# main.net
KiCad netlist of a schematic drawn in Altium Designer
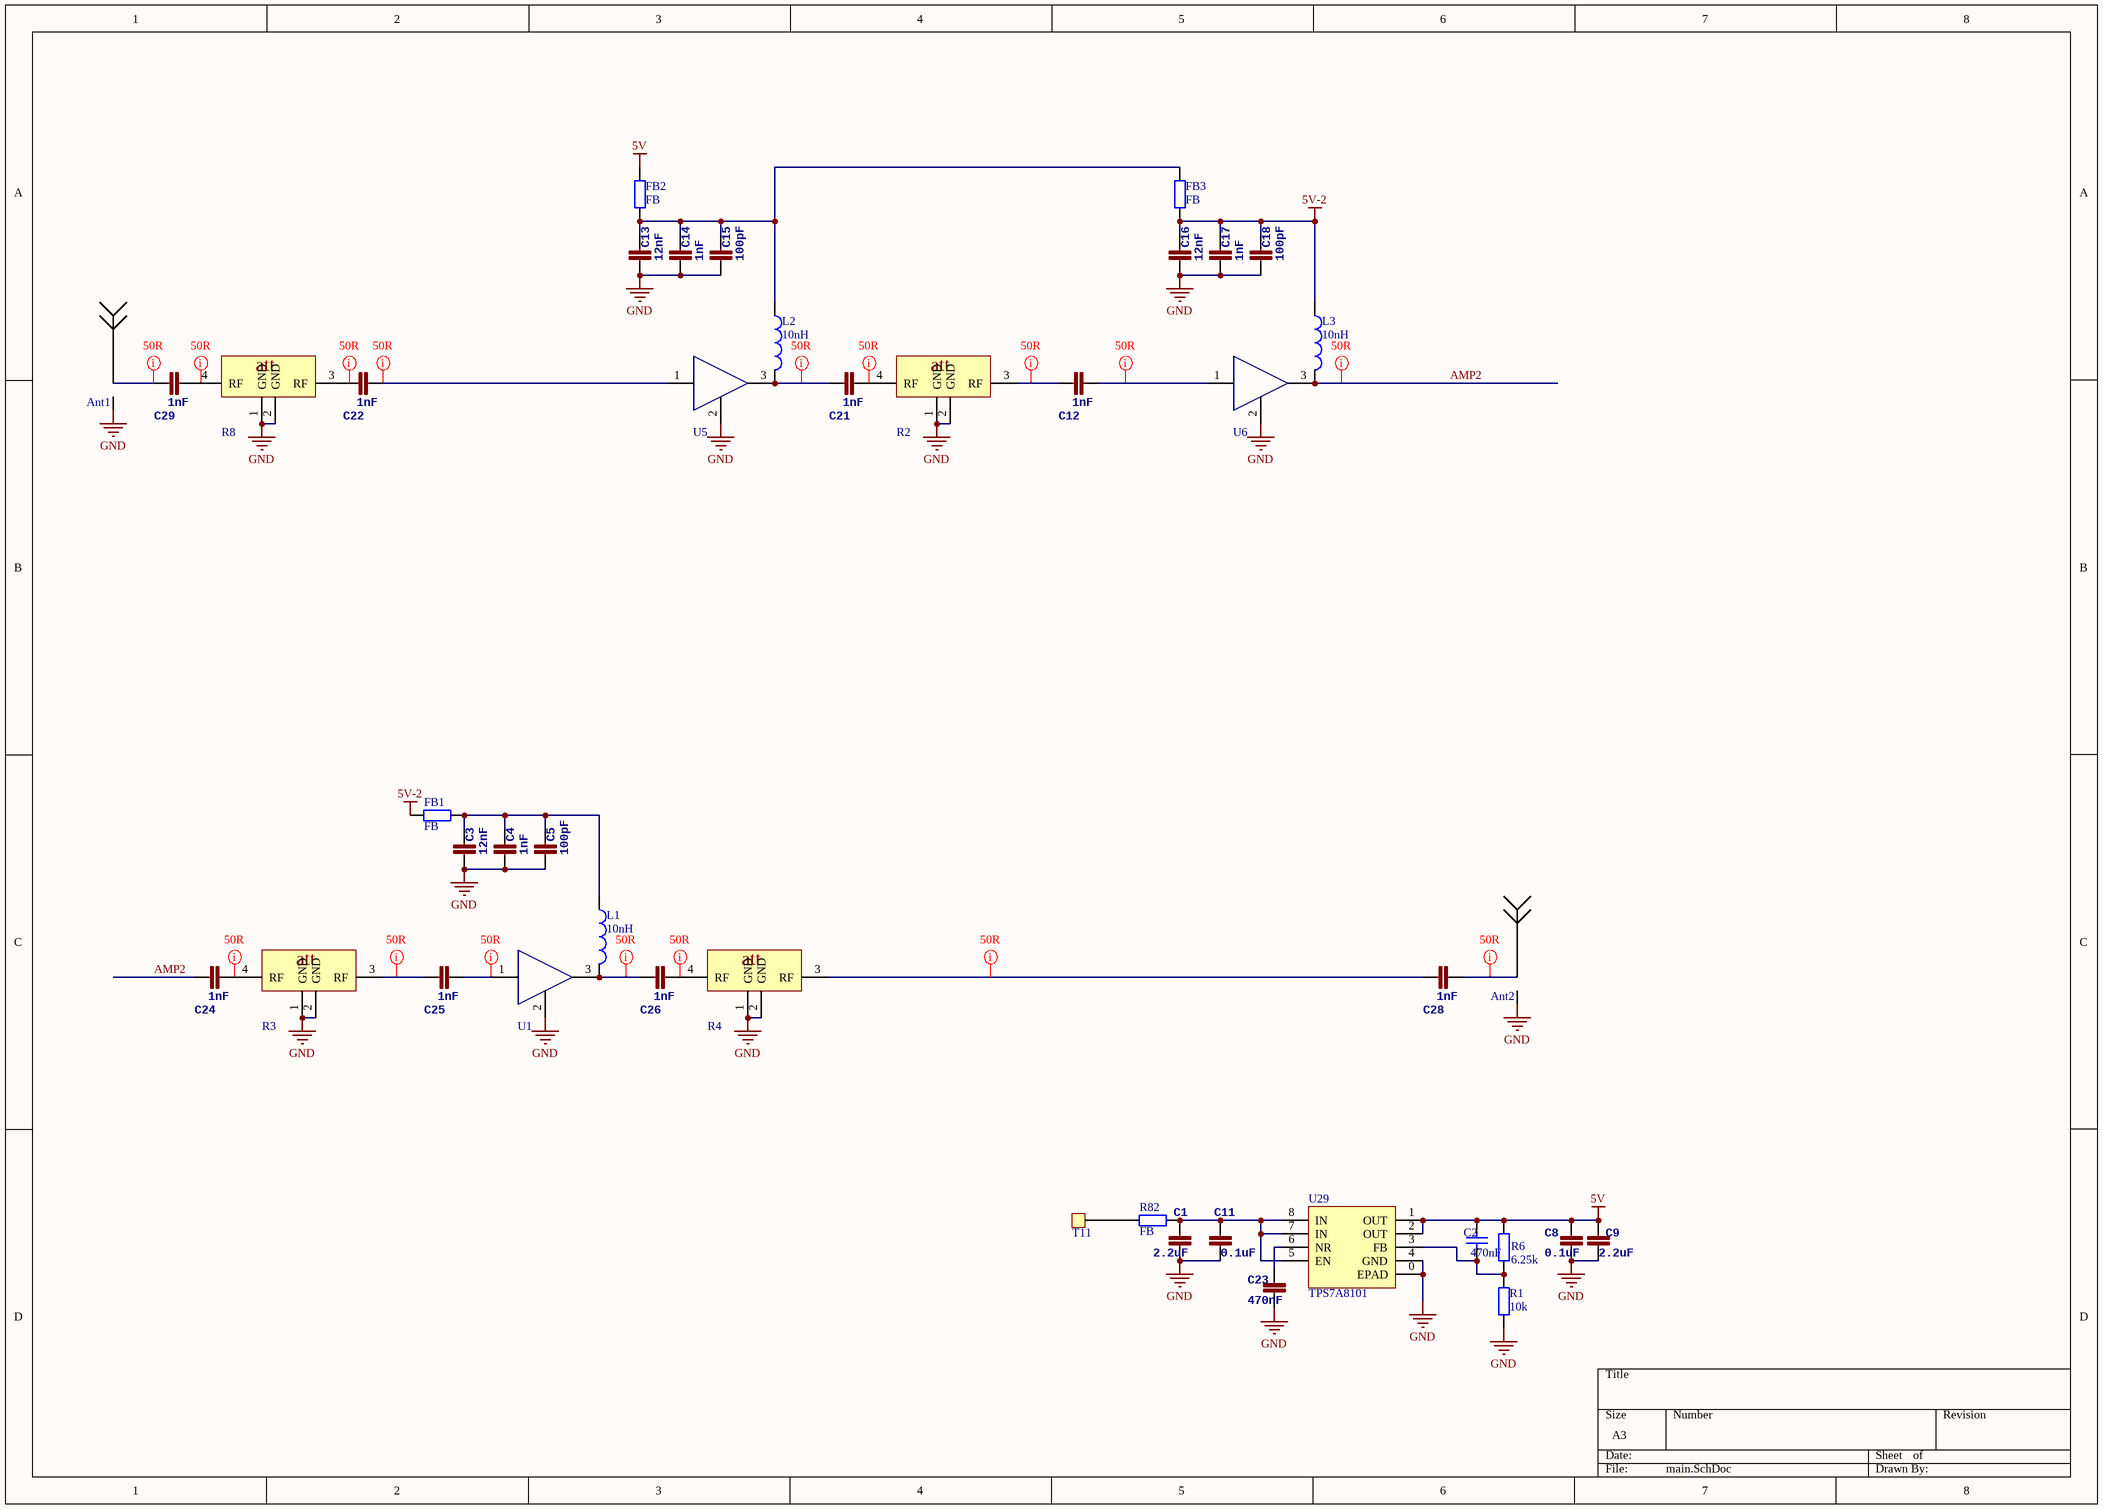
[diagram p0: main.SchDoc]

(export (version "E")
  (design (tool "Eeschema 10.0.6"))
  (components
    (comp (ref "Ant1") (value "Antenna") (footprint "SMA-2") (libsource (lib "F4SDR") (part "Antenna")))
    (comp (ref "Ant2") (value "Antenna") (footprint "SMA-2") (libsource (lib "F4SDR") (part "Antenna")))
    (comp (ref "C1")
      (value "2.2uF")
      (footprint "0603")
      (description "<b>Capacitor</b>\nStandard 0603 ceramic capacitor, and 0.1\" leaded capacitor.")
      (fields (field (name "PARTNO") "CC0402ZRY5V7BB104"))
      (libsource (lib "") (part "CAP0402-CAP_1"))
    )
    (comp (ref "C2")
      (value "470nF")
      (footprint "0402")
      (description "Capacitor")
      (fields (field (name "PUBLISHER") "Altium Limited"))
      (libsource (lib "RTC6705") (part "Cap"))
    )
    (comp (ref "C3")
      (value "12nF")
      (footprint "0805")
      (description "<b>Capacitor</b>\nStandard 0603 ceramic capacitor, and 0.1\" leaded capacitor.")
      (fields (field (name "PARTNO") "CC0402ZRY5V7BB104"))
      (libsource (lib "") (part "CAP0402-CAP_1"))
    )
    (comp (ref "C4")
      (value "1nF")
      (footprint "0402")
      (description "<b>Capacitor</b>\nStandard 0603 ceramic capacitor, and 0.1\" leaded capacitor.")
      (fields (field (name "PARTNO") "CC0402ZRY5V7BB104"))
      (libsource (lib "") (part "CAP0402-CAP_1"))
    )
    (comp (ref "C5")
      (value "100pF")
      (footprint "0402")
      (description "<b>Capacitor</b>\nStandard 0603 ceramic capacitor, and 0.1\" leaded capacitor.")
      (fields (field (name "PARTNO") "CC0402ZRY5V7BB104"))
      (libsource (lib "") (part "CAP0402-CAP_1"))
    )
    (comp (ref "C8")
      (value "0.1uF")
      (footprint "0603")
      (description "<b>Capacitor</b>\nStandard 0603 ceramic capacitor, and 0.1\" leaded capacitor.")
      (fields (field (name "PARTNO") "CC0402ZRY5V7BB104"))
      (libsource (lib "*") (part "CAP0402-CAP"))
    )
    (comp (ref "C9")
      (value "2.2uF")
      (footprint "0603")
      (description "<b>Capacitor</b>\nStandard 0603 ceramic capacitor, and 0.1\" leaded capacitor.")
      (fields (field (name "PARTNO") "CC0402ZRY5V7BB104"))
      (libsource (lib "") (part "CAP0402-CAP_1"))
    )
    (comp (ref "C11")
      (value "0.1uF")
      (footprint "0402")
      (description "<b>Capacitor</b>\nStandard 0603 ceramic capacitor, and 0.1\" leaded capacitor.")
      (fields (field (name "PARTNO") "CC0402ZRY5V7BB104"))
      (libsource (lib "*") (part "CAP0402-CAP"))
    )
    (comp (ref "C12")
      (value "1nF")
      (footprint "0402")
      (description "<b>Capacitor</b>\nStandard 0603 ceramic capacitor, and 0.1\" leaded capacitor.")
      (fields (field (name "PARTNO") "CC0402ZRY5V7BB104"))
      (libsource (lib "pixhawk2") (part "CAP0402-CAP"))
    )
    (comp (ref "C13")
      (value "12nF")
      (footprint "0805")
      (description "<b>Capacitor</b>\nStandard 0603 ceramic capacitor, and 0.1\" leaded capacitor.")
      (fields (field (name "PARTNO") "CC0402ZRY5V7BB104"))
      (libsource (lib "") (part "CAP0402-CAP_1"))
    )
    (comp (ref "C14")
      (value "1nF")
      (footprint "0402")
      (description "<b>Capacitor</b>\nStandard 0603 ceramic capacitor, and 0.1\" leaded capacitor.")
      (fields (field (name "PARTNO") "CC0402ZRY5V7BB104"))
      (libsource (lib "") (part "CAP0402-CAP_1"))
    )
    (comp (ref "C15")
      (value "100pF")
      (footprint "0402")
      (description "<b>Capacitor</b>\nStandard 0603 ceramic capacitor, and 0.1\" leaded capacitor.")
      (fields (field (name "PARTNO") "CC0402ZRY5V7BB104"))
      (libsource (lib "") (part "CAP0402-CAP_1"))
    )
    (comp (ref "C16")
      (value "12nF")
      (footprint "0805")
      (description "<b>Capacitor</b>\nStandard 0603 ceramic capacitor, and 0.1\" leaded capacitor.")
      (fields (field (name "PARTNO") "CC0402ZRY5V7BB104"))
      (libsource (lib "") (part "CAP0402-CAP_1"))
    )
    (comp (ref "C17")
      (value "1nF")
      (footprint "0402")
      (description "<b>Capacitor</b>\nStandard 0603 ceramic capacitor, and 0.1\" leaded capacitor.")
      (fields (field (name "PARTNO") "CC0402ZRY5V7BB104"))
      (libsource (lib "") (part "CAP0402-CAP_1"))
    )
    (comp (ref "C18")
      (value "100pF")
      (footprint "0402")
      (description "<b>Capacitor</b>\nStandard 0603 ceramic capacitor, and 0.1\" leaded capacitor.")
      (fields (field (name "PARTNO") "CC0402ZRY5V7BB104"))
      (libsource (lib "") (part "CAP0402-CAP_1"))
    )
    (comp (ref "C21")
      (value "1nF")
      (footprint "0402")
      (description "<b>Capacitor</b>\nStandard 0603 ceramic capacitor, and 0.1\" leaded capacitor.")
      (fields (field (name "PARTNO") "CC0402ZRY5V7BB104"))
      (libsource (lib "pixhawk2") (part "CAP0402-CAP"))
    )
    (comp (ref "C22")
      (value "1nF")
      (footprint "0402")
      (description "<b>Capacitor</b>\nStandard 0603 ceramic capacitor, and 0.1\" leaded capacitor.")
      (fields (field (name "PARTNO") "CC0402ZRY5V7BB104"))
      (libsource (lib "pixhawk2") (part "CAP0402-CAP"))
    )
    (comp (ref "C23")
      (value "470nF")
      (footprint "0402")
      (description "<b>Capacitor</b>\nStandard 0603 ceramic capacitor, and 0.1\" leaded capacitor.")
      (fields (field (name "PARTNO") "CC0402ZRY5V7BB104"))
      (libsource (lib "*") (part "CAP0402-CAP"))
    )
    (comp (ref "C24")
      (value "1nF")
      (footprint "0402")
      (description "<b>Capacitor</b>\nStandard 0603 ceramic capacitor, and 0.1\" leaded capacitor.")
      (fields (field (name "PARTNO") "CC0402ZRY5V7BB104"))
      (libsource (lib "pixhawk2") (part "CAP0402-CAP"))
    )
    (comp (ref "C25")
      (value "1nF")
      (footprint "0402")
      (description "<b>Capacitor</b>\nStandard 0603 ceramic capacitor, and 0.1\" leaded capacitor.")
      (fields (field (name "PARTNO") "CC0402ZRY5V7BB104"))
      (libsource (lib "pixhawk2") (part "CAP0402-CAP"))
    )
    (comp (ref "C26")
      (value "1nF")
      (footprint "0402")
      (description "<b>Capacitor</b>\nStandard 0603 ceramic capacitor, and 0.1\" leaded capacitor.")
      (fields (field (name "PARTNO") "CC0402ZRY5V7BB104"))
      (libsource (lib "pixhawk2") (part "CAP0402-CAP"))
    )
    (comp (ref "C28")
      (value "1nF")
      (footprint "0402")
      (description "<b>Capacitor</b>\nStandard 0603 ceramic capacitor, and 0.1\" leaded capacitor.")
      (fields (field (name "PARTNO") "CC0402ZRY5V7BB104"))
      (libsource (lib "pixhawk2") (part "CAP0402-CAP"))
    )
    (comp (ref "C29")
      (value "1nF")
      (footprint "0402")
      (description "<b>Capacitor</b>\nStandard 0603 ceramic capacitor, and 0.1\" leaded capacitor.")
      (fields (field (name "PARTNO") "CC0402ZRY5V7BB104"))
      (libsource (lib "pixhawk2") (part "CAP0402-CAP"))
    )
    (comp (ref "FB1")
      (value "FB")
      (footprint "0603")
      (description "Resistor")
      (fields (field (name "PUBLISHER") "Altium Limited"))
      (libsource (lib "") (part "Res2_3"))
    )
    (comp (ref "FB2")
      (value "FB")
      (footprint "0603")
      (description "Resistor")
      (fields (field (name "PUBLISHER") "Altium Limited"))
      (libsource (lib "") (part "Res2_2"))
    )
    (comp (ref "FB3")
      (value "FB")
      (footprint "0603")
      (description "Resistor")
      (fields (field (name "PUBLISHER") "Altium Limited"))
      (libsource (lib "") (part "Res2_2"))
    )
    (comp (ref "L1")
      (value "10nH")
      (footprint "0402")
      (description "Inductor")
      (fields (field (name "PUBLISHER") "Altium Limited"))
      (libsource (lib "Miscellaneous Devices") (part "Inductor"))
    )
    (comp (ref "L2")
      (value "10nH")
      (footprint "0402")
      (description "Inductor")
      (fields (field (name "PUBLISHER") "Altium Limited"))
      (libsource (lib "Miscellaneous Devices") (part "Inductor"))
    )
    (comp (ref "L3")
      (value "10nH")
      (footprint "0402")
      (description "Inductor")
      (fields (field (name "PUBLISHER") "Altium Limited"))
      (libsource (lib "Miscellaneous Devices") (part "Inductor"))
    )
    (comp (ref "R1")
      (value "10k")
      (footprint "0402")
      (description "Resistor")
      (fields (field (name "PUBLISHER") "Altium Limited"))
      (libsource (lib "") (part "Res2_1"))
    )
    (comp (ref "R2")
      (value "EXB24-RF-ATT")
      (footprint "EXB24AT-RF-ATT")
      (libsource (lib "F4SDR") (part "EXB24-RF-ATT"))
    )
    (comp (ref "R3")
      (value "EXB24-RF-ATT")
      (footprint "EXB24AT-RF-ATT")
      (libsource (lib "F4SDR") (part "EXB24-RF-ATT"))
    )
    (comp (ref "R4")
      (value "EXB24-RF-ATT")
      (footprint "EXB24AT-RF-ATT")
      (libsource (lib "F4SDR") (part "EXB24-RF-ATT"))
    )
    (comp (ref "R6")
      (value "6.25k")
      (footprint "0402")
      (description "Resistor")
      (fields (field (name "PUBLISHER") "Altium Limited"))
      (libsource (lib "") (part "Res2_1"))
    )
    (comp (ref "R8")
      (value "EXB24-RF-ATT")
      (footprint "EXB24AT-RF-ATT")
      (libsource (lib "F4SDR") (part "EXB24-RF-ATT"))
    )
    (comp (ref "R82")
      (value "FB")
      (footprint "0603L")
      (description "Resistor")
      (fields (field (name "PUBLISHER") "Altium Limited"))
      (libsource (lib "Miscellaneous Devices") (part "Res2"))
    )
    (comp (ref "T11") (value "TestPad") (footprint "TestPad - 1mm") (libsource (lib "sch") (part "TestPad")))
    (comp (ref "U1") (value "AMP-SOT89") (footprint "SOT-89") (libsource (lib "F4SDR") (part "AMP-SOT89")))
    (comp (ref "U5") (value "AMP-SOT89") (footprint "SOT-89") (libsource (lib "F4SDR") (part "AMP-SOT89")))
    (comp (ref "U6") (value "AMP-SOT89") (footprint "SOT-89") (libsource (lib "F4SDR") (part "AMP-SOT89")))
    (comp (ref "U29")
      (value "TPS7A8101")
      (footprint "TPS7A8101")
      (libsource (lib "F4SDR") (part "TPS7A8101"))
    )
  )
  (nets
    (net (code "1") (name "/AMP2") (class "Default")
      (node (ref "C24") (pin "1") (pinfunction "1_1") (pintype "passive"))
      (node (ref "L3") (pin "2") (pinfunction "2_2") (pintype "passive"))
      (node (ref "U6") (pin "3") (pinfunction "3_3") (pintype "passive"))
    )
    (net (code "2") (name "5V") (class "Default")
      (node (ref "C2") (pin "1") (pinfunction "1_1") (pintype "passive"))
      (node (ref "C8") (pin "2") (pinfunction "2_2") (pintype "passive"))
      (node (ref "C9") (pin "2") (pinfunction "2_2") (pintype "passive"))
      (node (ref "FB2") (pin "2") (pinfunction "2_2") (pintype "passive"))
      (node (ref "R6") (pin "1") (pinfunction "1_1") (pintype "passive"))
      (node (ref "U29") (pin "1") (pinfunction "OUT_1") (pintype "passive"))
      (node (ref "U29") (pin "2") (pinfunction "OUT_2") (pintype "passive"))
    )
    (net (code "3") (name "5V-2") (class "Default")
      (node (ref "C16") (pin "2") (pinfunction "2_2") (pintype "passive"))
      (node (ref "C17") (pin "2") (pinfunction "2_2") (pintype "passive"))
      (node (ref "C18") (pin "2") (pinfunction "2_2") (pintype "passive"))
      (node (ref "FB1") (pin "1") (pinfunction "1_1") (pintype "passive"))
      (node (ref "FB3") (pin "1") (pinfunction "1_1") (pintype "passive"))
      (node (ref "L3") (pin "1") (pinfunction "1_1") (pintype "passive"))
    )
    (net (code "4") (name "GND") (class "Default")
      (node (ref "Ant1") (pin "GND") (pinfunction "G_GND") (pintype "passive"))
      (node (ref "Ant2") (pin "GND") (pinfunction "G_GND") (pintype "passive"))
      (node (ref "C1") (pin "1") (pinfunction "1_1") (pintype "passive"))
      (node (ref "C11") (pin "1") (pinfunction "1_1") (pintype "passive"))
      (node (ref "C13") (pin "1") (pinfunction "1_1") (pintype "passive"))
      (node (ref "C14") (pin "1") (pinfunction "1_1") (pintype "passive"))
      (node (ref "C15") (pin "1") (pinfunction "1_1") (pintype "passive"))
      (node (ref "C16") (pin "1") (pinfunction "1_1") (pintype "passive"))
      (node (ref "C17") (pin "1") (pinfunction "1_1") (pintype "passive"))
      (node (ref "C18") (pin "1") (pinfunction "1_1") (pintype "passive"))
      (node (ref "C23") (pin "1") (pinfunction "1_1") (pintype "passive"))
      (node (ref "C3") (pin "1") (pinfunction "1_1") (pintype "passive"))
      (node (ref "C4") (pin "1") (pinfunction "1_1") (pintype "passive"))
      (node (ref "C5") (pin "1") (pinfunction "1_1") (pintype "passive"))
      (node (ref "C8") (pin "1") (pinfunction "1_1") (pintype "passive"))
      (node (ref "C9") (pin "1") (pinfunction "1_1") (pintype "passive"))
      (node (ref "R1") (pin "2") (pinfunction "2_2") (pintype "passive"))
      (node (ref "R2") (pin "1") (pinfunction "GND_1") (pintype "passive"))
      (node (ref "R2") (pin "2") (pinfunction "GND_2") (pintype "passive"))
      (node (ref "R3") (pin "1") (pinfunction "GND_1") (pintype "passive"))
      (node (ref "R3") (pin "2") (pinfunction "GND_2") (pintype "passive"))
      (node (ref "R4") (pin "1") (pinfunction "GND_1") (pintype "passive"))
      (node (ref "R4") (pin "2") (pinfunction "GND_2") (pintype "passive"))
      (node (ref "R8") (pin "1") (pinfunction "GND_1") (pintype "passive"))
      (node (ref "R8") (pin "2") (pinfunction "GND_2") (pintype "passive"))
      (node (ref "U1") (pin "2") (pinfunction "2_2") (pintype "passive"))
      (node (ref "U29") (pin "0") (pinfunction "EPAD_0") (pintype "passive"))
      (node (ref "U29") (pin "4") (pinfunction "GND_4") (pintype "passive"))
      (node (ref "U5") (pin "2") (pinfunction "2_2") (pintype "passive"))
      (node (ref "U6") (pin "2") (pinfunction "2_2") (pintype "passive"))
    )
    (net (code "5") (name "Net-(Ant1-Pad1)") (class "Default")
      (node (ref "Ant1") (pin "1") (pinfunction "1_1") (pintype "passive"))
      (node (ref "C29") (pin "1") (pinfunction "1_1") (pintype "passive"))
    )
    (net (code "6") (name "Net-(Ant2-Pad1)") (class "Default")
      (node (ref "Ant2") (pin "1") (pinfunction "1_1") (pintype "passive"))
      (node (ref "C28") (pin "2") (pinfunction "2_2") (pintype "passive"))
    )
    (net (code "7") (name "Net-(C3-Pad2)") (class "Default")
      (node (ref "C3") (pin "2") (pinfunction "2_2") (pintype "passive"))
      (node (ref "C4") (pin "2") (pinfunction "2_2") (pintype "passive"))
      (node (ref "C5") (pin "2") (pinfunction "2_2") (pintype "passive"))
      (node (ref "FB1") (pin "2") (pinfunction "2_2") (pintype "passive"))
      (node (ref "L1") (pin "1") (pinfunction "1_1") (pintype "passive"))
    )
    (net (code "8") (name "Net-(C12-Pad1)") (class "Default")
      (node (ref "C12") (pin "1") (pinfunction "1_1") (pintype "passive"))
      (node (ref "R2") (pin "3") (pinfunction "RF_3") (pintype "passive"))
    )
    (net (code "9") (name "Net-(C12-Pad2)") (class "Default")
      (node (ref "C12") (pin "2") (pinfunction "2_2") (pintype "passive"))
      (node (ref "U6") (pin "1") (pinfunction "1_1") (pintype "passive"))
    )
    (net (code "10") (name "Net-(C13-Pad2)") (class "Default")
      (node (ref "C13") (pin "2") (pinfunction "2_2") (pintype "passive"))
      (node (ref "C14") (pin "2") (pinfunction "2_2") (pintype "passive"))
      (node (ref "C15") (pin "2") (pinfunction "2_2") (pintype "passive"))
      (node (ref "FB2") (pin "1") (pinfunction "1_1") (pintype "passive"))
      (node (ref "FB3") (pin "2") (pinfunction "2_2") (pintype "passive"))
      (node (ref "L2") (pin "1") (pinfunction "1_1") (pintype "passive"))
    )
    (net (code "11") (name "Net-(C21-Pad1)") (class "Default")
      (node (ref "C21") (pin "1") (pinfunction "1_1") (pintype "passive"))
      (node (ref "L2") (pin "2") (pinfunction "2_2") (pintype "passive"))
      (node (ref "U5") (pin "3") (pinfunction "3_3") (pintype "passive"))
    )
    (net (code "12") (name "Net-(C21-Pad2)") (class "Default")
      (node (ref "C21") (pin "2") (pinfunction "2_2") (pintype "passive"))
      (node (ref "R2") (pin "4") (pinfunction "RF_4") (pintype "passive"))
    )
    (net (code "13") (name "Net-(C22-Pad1)") (class "Default")
      (node (ref "C22") (pin "1") (pinfunction "1_1") (pintype "passive"))
      (node (ref "R8") (pin "3") (pinfunction "RF_3") (pintype "passive"))
    )
    (net (code "14") (name "Net-(C22-Pad2)") (class "Default")
      (node (ref "C22") (pin "2") (pinfunction "2_2") (pintype "passive"))
      (node (ref "U5") (pin "1") (pinfunction "1_1") (pintype "passive"))
    )
    (net (code "15") (name "Net-(C24-Pad2)") (class "Default")
      (node (ref "C24") (pin "2") (pinfunction "2_2") (pintype "passive"))
      (node (ref "R3") (pin "4") (pinfunction "RF_4") (pintype "passive"))
    )
    (net (code "16") (name "Net-(C25-Pad1)") (class "Default")
      (node (ref "C25") (pin "1") (pinfunction "1_1") (pintype "passive"))
      (node (ref "R3") (pin "3") (pinfunction "RF_3") (pintype "passive"))
    )
    (net (code "17") (name "Net-(C25-Pad2)") (class "Default")
      (node (ref "C25") (pin "2") (pinfunction "2_2") (pintype "passive"))
      (node (ref "U1") (pin "1") (pinfunction "1_1") (pintype "passive"))
    )
    (net (code "18") (name "Net-(C26-Pad1)") (class "Default")
      (node (ref "C26") (pin "1") (pinfunction "1_1") (pintype "passive"))
      (node (ref "L1") (pin "2") (pinfunction "2_2") (pintype "passive"))
      (node (ref "U1") (pin "3") (pinfunction "3_3") (pintype "passive"))
    )
    (net (code "19") (name "Net-(C26-Pad2)") (class "Default")
      (node (ref "C26") (pin "2") (pinfunction "2_2") (pintype "passive"))
      (node (ref "R4") (pin "4") (pinfunction "RF_4") (pintype "passive"))
    )
    (net (code "20") (name "Net-(C28-Pad1)") (class "Default")
      (node (ref "C28") (pin "1") (pinfunction "1_1") (pintype "passive"))
      (node (ref "R4") (pin "3") (pinfunction "RF_3") (pintype "passive"))
    )
    (net (code "21") (name "Net-(C29-Pad2)") (class "Default")
      (node (ref "C29") (pin "2") (pinfunction "2_2") (pintype "passive"))
      (node (ref "R8") (pin "4") (pinfunction "RF_4") (pintype "passive"))
    )
    (net (code "22") (name "Net-(T11-3)") (class "Default")
      (node (ref "R82") (pin "2") (pinfunction "2_2") (pintype "passive"))
      (node (ref "T11") (pin "1") (pinfunction "3_1") (pintype "passive"))
    )
    (net (code "23") (name "Net-(U29-EN)") (class "Default")
      (node (ref "C1") (pin "2") (pinfunction "2_2") (pintype "passive"))
      (node (ref "C11") (pin "2") (pinfunction "2_2") (pintype "passive"))
      (node (ref "R82") (pin "1") (pinfunction "1_1") (pintype "passive"))
      (node (ref "U29") (pin "5") (pinfunction "EN_5") (pintype "passive"))
      (node (ref "U29") (pin "7") (pinfunction "IN_7") (pintype "passive"))
      (node (ref "U29") (pin "8") (pinfunction "IN_8") (pintype "passive"))
    )
    (net (code "24") (name "Net-(U29-FB)") (class "Default")
      (node (ref "C2") (pin "2") (pinfunction "2_2") (pintype "passive"))
      (node (ref "R1") (pin "1") (pinfunction "1_1") (pintype "passive"))
      (node (ref "R6") (pin "2") (pinfunction "2_2") (pintype "passive"))
      (node (ref "U29") (pin "3") (pinfunction "FB_3") (pintype "passive"))
    )
    (net (code "25") (name "Net-(U29-NR)") (class "Default")
      (node (ref "C23") (pin "2") (pinfunction "2_2") (pintype "passive"))
      (node (ref "U29") (pin "6") (pinfunction "NR_6") (pintype "passive"))
    )
  )
)
